# TC364_MainBoard_Singal_V2_0.net
KiCad netlist of a schematic drawn in Altium Designer
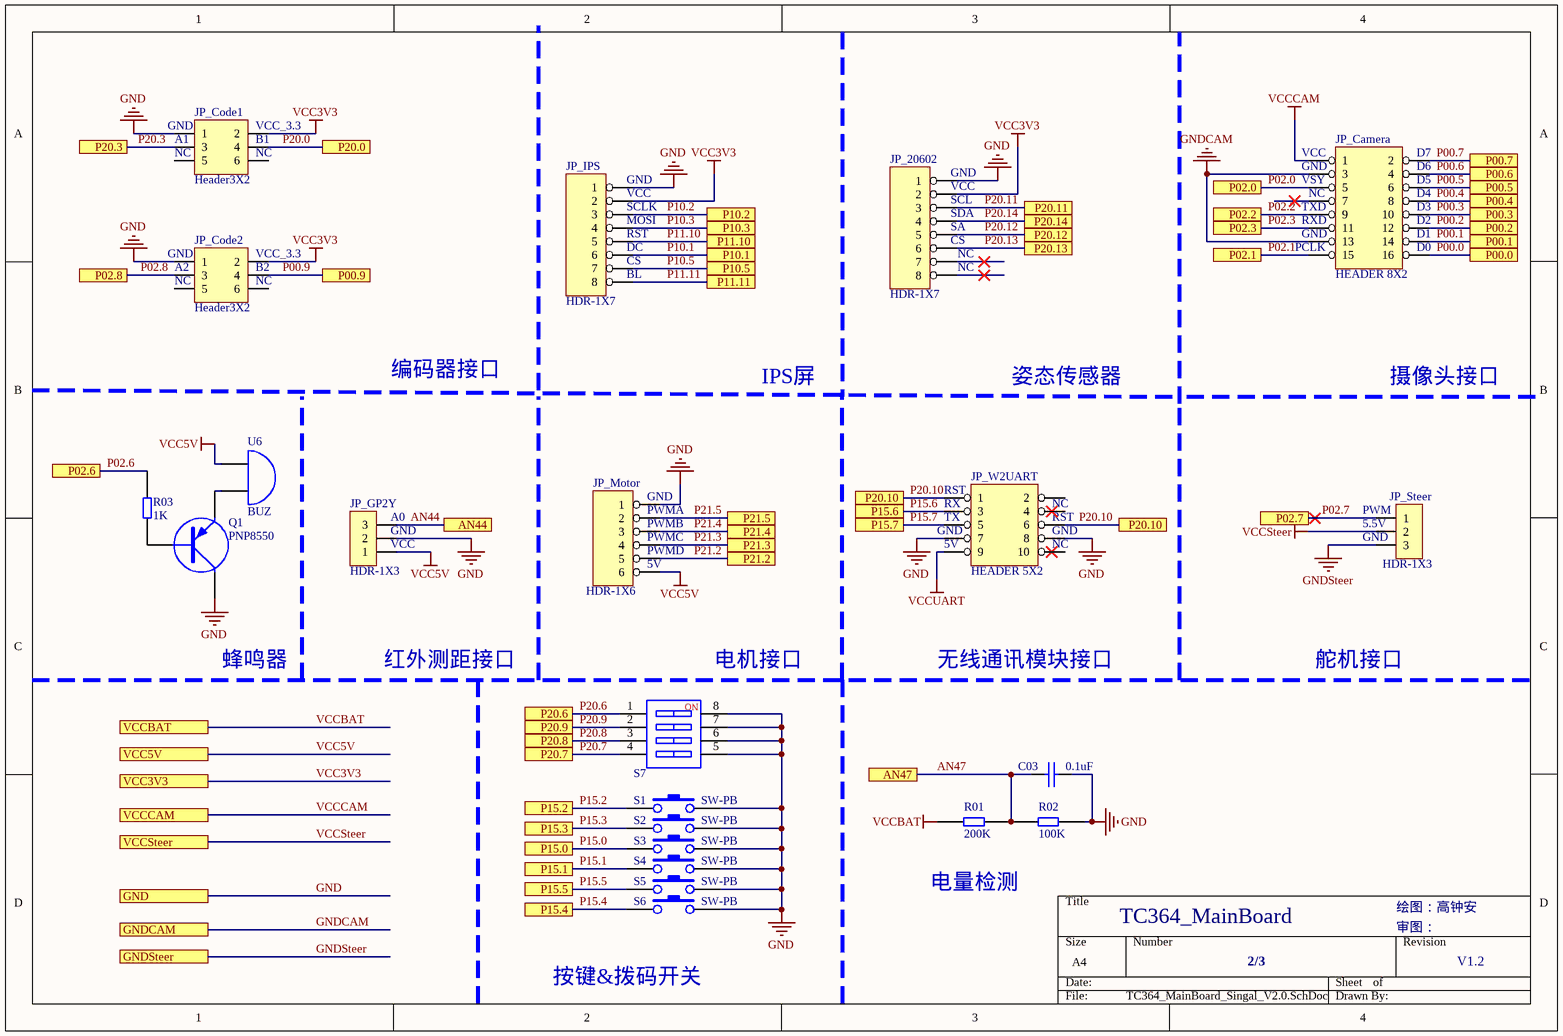
[diagram p0: TC364_MainBoard_Singal_V2.0.SchDoc]

(export (version "E")
  (design (tool "Eeschema 10.0.6"))
  (components
    (comp (ref "C03")
      (value "0.1uF")
      (footprint "0805C")
      (description "Capacitor")
      (libsource (lib "Protel99Lib_SCH") (part "CAP"))
    )
    (comp (ref "JP_20602")
      (value "HDR-1X7")
      (footprint "SIP8")
      (description "8 Pin Header")
      (libsource (lib "Protel99Lib_SCH") (part "8 HEADER"))
    )
    (comp (ref "JP_Camera")
      (value "HEADER 8X2")
      (footprint "IDC16-JLC - duplicate")
      (libsource (lib "Protel99Lib_SCH") (part "HEADER 8X2"))
    )
    (comp (ref "JP_Code1")
      (value "Header3X2")
      (footprint "HDR2.54-LI-2x3P")
      (description "3*2P接插件")
      (fields (field (name "版权归属") "封装库来自淘宝 ID：黄晶宝石"))
      (libsource (lib "5.3 - 接插件-脚距2.54 (100mil) ") (part "Header 3X2"))
    )
    (comp (ref "JP_Code2")
      (value "Header3X2")
      (footprint "HDR2.54-LI-2x3P")
      (description "3*2P接插件")
      (fields (field (name "版权归属") "封装库来自淘宝 ID：黄晶宝石"))
      (libsource (lib "5.3 - 接插件-脚距2.54 (100mil) ") (part "Header 3X2"))
    )
    (comp (ref "JP_GP2Y")
      (value "HDR-1X3")
      (footprint "SIP3N")
      (description "3P接插件")
      (fields (field (name "版权归属") "封装库来自淘宝 ID：黄晶宝石"))
      (libsource (lib "5.3 - 接插件-脚距2.54 (100mil) ") (part "Header 3"))
    )
    (comp (ref "JP_IPS")
      (value "HDR-1X7")
      (footprint "SIP8")
      (description "8 Pin Header")
      (libsource (lib "Protel99Lib_SCH") (part "8 HEADER"))
    )
    (comp (ref "JP_Motor")
      (value "HDR-1X6")
      (footprint "SIP6N")
      (libsource (lib "Protel99Lib_SCH") (part "HEADER 6"))
    )
    (comp (ref "JP_Steer")
      (value "HDR-1X3")
      (footprint "HDR2.54-LI-3P")
      (description "3P接插件")
      (fields (field (name "版权归属") "封装库来自淘宝 ID：黄晶宝石"))
      (libsource (lib "") (part "Header 3_1"))
    )
    (comp (ref "JP_W2UART")
      (value "HEADER 5X2")
      (footprint "IDC10-JLC")
      (libsource (lib "Protel99Lib_SCH") (part "HEADER 5X2"))
    )
    (comp (ref "Q1")
      (value "PNP8550")
      (footprint "PNP8550-SO")
      (description "PNP Transistor")
      (libsource (lib "Protel99Lib_SCH") (part "PNP"))
    )
    (comp (ref "R01") (value "200K") (footprint "0805R") (libsource (lib "BaseLib_SCH") (part "RES")))
    (comp (ref "R02") (value "100K") (footprint "0805R") (libsource (lib "BaseLib_SCH") (part "RES")))
    (comp (ref "R03") (value "1K") (footprint "0805R") (libsource (lib "BaseLib_SCH") (part "RES")))
    (comp (ref "S1")
      (value "SW-PB")
      (footprint "KEY2-6X3")
      (description "按键")
      (libsource (lib "jianing") (part "SW-PB"))
    )
    (comp (ref "S2")
      (value "SW-PB")
      (footprint "KEY2-6X3")
      (description "按键")
      (libsource (lib "jianing") (part "SW-PB"))
    )
    (comp (ref "S3")
      (value "SW-PB")
      (footprint "KEY2-6X3")
      (description "按键")
      (libsource (lib "jianing") (part "SW-PB"))
    )
    (comp (ref "S4")
      (value "SW-PB")
      (footprint "KEY2-6X3")
      (description "按键")
      (libsource (lib "jianing") (part "SW-PB"))
    )
    (comp (ref "S5")
      (value "SW-PB")
      (footprint "KEY2-6X3")
      (description "按键")
      (libsource (lib "jianing") (part "SW-PB"))
    )
    (comp (ref "S6")
      (value "SW-PB")
      (footprint "KEY2-6X3")
      (description "按键")
      (libsource (lib "jianing") (part "SW-PB"))
    )
    (comp (ref "S7")
      (value "SW-4P")
      (footprint "CSW DIP-4P")
      (description "4路编码开关")
      (libsource (lib "0.7 - 常用按键-开关") (part "SW-4P"))
    )
    (comp (ref "U6")
      (value "BUZ")
      (footprint "BUZ")
      (description "Bell")
      (libsource (lib "Protel99Lib_SCH") (part "BELL"))
    )
  )
  (nets
    (net (code "2") (name "/AN44") (class "Default")
      (node (ref "JP_GP2Y") (pin "3") (pinfunction "3_3") (pintype "passive"))
    )
    (net (code "3") (name "/AN47") (class "Default")
      (node (ref "C03") (pin "1") (pinfunction "1_1") (pintype "passive"))
      (node (ref "R01") (pin "1") (pinfunction "1_1") (pintype "passive"))
      (node (ref "R02") (pin "2") (pinfunction "2_2") (pintype "passive"))
    )
    (net (code "4") (name "/P00.0") (class "Default")
      (node (ref "JP_Camera") (pin "16") (pinfunction "16_16") (pintype "passive"))
    )
    (net (code "5") (name "/P00.1") (class "Default")
      (node (ref "JP_Camera") (pin "14") (pinfunction "14_14") (pintype "passive"))
    )
    (net (code "6") (name "/P00.2") (class "Default")
      (node (ref "JP_Camera") (pin "12") (pinfunction "12_12") (pintype "passive"))
    )
    (net (code "7") (name "/P00.3") (class "Default")
      (node (ref "JP_Camera") (pin "10") (pinfunction "10_10") (pintype "passive"))
    )
    (net (code "8") (name "/P00.4") (class "Default")
      (node (ref "JP_Camera") (pin "8") (pinfunction "8_8") (pintype "passive"))
    )
    (net (code "9") (name "/P00.5") (class "Default")
      (node (ref "JP_Camera") (pin "6") (pinfunction "6_6") (pintype "passive"))
    )
    (net (code "10") (name "/P00.6") (class "Default")
      (node (ref "JP_Camera") (pin "4") (pinfunction "4_4") (pintype "passive"))
    )
    (net (code "11") (name "/P00.7") (class "Default")
      (node (ref "JP_Camera") (pin "2") (pinfunction "2_2") (pintype "passive"))
    )
    (net (code "12") (name "/P00.9") (class "Default")
      (node (ref "JP_Code2") (pin "4") (pinfunction "4_4") (pintype "passive"))
    )
    (net (code "13") (name "/P02.0") (class "Default")
      (node (ref "JP_Camera") (pin "5") (pinfunction "5_5") (pintype "passive"))
    )
    (net (code "14") (name "/P02.1") (class "Default")
      (node (ref "JP_Camera") (pin "15") (pinfunction "15_15") (pintype "passive"))
    )
    (net (code "15") (name "/P02.2") (class "Default")
      (node (ref "JP_Camera") (pin "9") (pinfunction "9_9") (pintype "passive"))
    )
    (net (code "16") (name "/P02.3") (class "Default")
      (node (ref "JP_Camera") (pin "11") (pinfunction "11_11") (pintype "passive"))
    )
    (net (code "17") (name "/P02.6") (class "Default")
      (node (ref "R03") (pin "1") (pinfunction "1_1") (pintype "passive"))
    )
    (net (code "18") (name "/P02.7") (class "Default")
      (node (ref "JP_Steer") (pin "1") (pinfunction "1_1") (pintype "passive"))
    )
    (net (code "19") (name "/P02.8") (class "Default")
      (node (ref "JP_Code2") (pin "3") (pinfunction "3_3") (pintype "passive"))
    )
    (net (code "20") (name "/P10.1") (class "Default")
      (node (ref "JP_IPS") (pin "6") (pinfunction "6_6") (pintype "passive"))
    )
    (net (code "21") (name "/P10.2") (class "Default")
      (node (ref "JP_IPS") (pin "3") (pinfunction "3_3") (pintype "passive"))
    )
    (net (code "22") (name "/P10.3") (class "Default")
      (node (ref "JP_IPS") (pin "4") (pinfunction "4_4") (pintype "passive"))
    )
    (net (code "23") (name "/P10.5") (class "Default")
      (node (ref "JP_IPS") (pin "7") (pinfunction "7_7") (pintype "passive"))
    )
    (net (code "24") (name "/P11.10") (class "Default")
      (node (ref "JP_IPS") (pin "5") (pinfunction "5_5") (pintype "passive"))
    )
    (net (code "25") (name "/P11.11") (class "Default")
      (node (ref "JP_IPS") (pin "8") (pinfunction "8_8") (pintype "passive"))
    )
    (net (code "26") (name "/P15.0") (class "Default")
      (node (ref "S3") (pin "1") (pinfunction "1_1") (pintype "passive"))
    )
    (net (code "27") (name "/P15.1") (class "Default")
      (node (ref "S4") (pin "1") (pinfunction "1_1") (pintype "passive"))
    )
    (net (code "28") (name "/P15.2") (class "Default")
      (node (ref "S1") (pin "1") (pinfunction "1_1") (pintype "passive"))
    )
    (net (code "29") (name "/P15.3") (class "Default")
      (node (ref "S2") (pin "1") (pinfunction "1_1") (pintype "passive"))
    )
    (net (code "30") (name "/P15.4") (class "Default")
      (node (ref "S6") (pin "1") (pinfunction "1_1") (pintype "passive"))
    )
    (net (code "31") (name "/P15.5") (class "Default")
      (node (ref "S5") (pin "1") (pinfunction "1_1") (pintype "passive"))
    )
    (net (code "32") (name "/P15.6") (class "Default")
      (node (ref "JP_W2UART") (pin "3") (pinfunction "3_3") (pintype "passive"))
    )
    (net (code "33") (name "/P15.7") (class "Default")
      (node (ref "JP_W2UART") (pin "5") (pinfunction "5_5") (pintype "passive"))
    )
    (net (code "34") (name "/P20.0") (class "Default")
      (node (ref "JP_Code1") (pin "4") (pinfunction "4_4") (pintype "passive"))
    )
    (net (code "35") (name "/P20.3") (class "Default")
      (node (ref "JP_Code1") (pin "3") (pinfunction "3_3") (pintype "passive"))
    )
    (net (code "36") (name "/P20.6") (class "Default")
      (node (ref "S7") (pin "1") (pinfunction "1_1") (pintype "passive"))
    )
    (net (code "37") (name "/P20.7") (class "Default")
      (node (ref "S7") (pin "4") (pinfunction "4_4") (pintype "passive"))
    )
    (net (code "38") (name "/P20.8") (class "Default")
      (node (ref "S7") (pin "3") (pinfunction "3_3") (pintype "passive"))
    )
    (net (code "39") (name "/P20.9") (class "Default")
      (node (ref "S7") (pin "2") (pinfunction "2_2") (pintype "passive"))
    )
    (net (code "40") (name "/P20.10") (class "Default")
      (node (ref "JP_W2UART") (pin "1") (pinfunction "1_1") (pintype "passive"))
      (node (ref "JP_W2UART") (pin "6") (pinfunction "6_6") (pintype "passive"))
    )
    (net (code "41") (name "/P20.11") (class "Default")
      (node (ref "JP_20602") (pin "3") (pinfunction "3_3") (pintype "passive"))
    )
    (net (code "42") (name "/P20.12") (class "Default")
      (node (ref "JP_20602") (pin "5") (pinfunction "5_5") (pintype "passive"))
    )
    (net (code "43") (name "/P20.13") (class "Default")
      (node (ref "JP_20602") (pin "6") (pinfunction "6_6") (pintype "passive"))
    )
    (net (code "44") (name "/P20.14") (class "Default")
      (node (ref "JP_20602") (pin "4") (pinfunction "4_4") (pintype "passive"))
    )
    (net (code "45") (name "/P21.2") (class "Default")
      (node (ref "JP_Motor") (pin "5") (pinfunction "5_5") (pintype "passive"))
    )
    (net (code "46") (name "/P21.3") (class "Default")
      (node (ref "JP_Motor") (pin "4") (pinfunction "4_4") (pintype "passive"))
    )
    (net (code "47") (name "/P21.4") (class "Default")
      (node (ref "JP_Motor") (pin "3") (pinfunction "3_3") (pintype "passive"))
    )
    (net (code "48") (name "/P21.5") (class "Default")
      (node (ref "JP_Motor") (pin "2") (pinfunction "2_2") (pintype "passive"))
    )
    (net (code "49") (name "GND") (class "Default")
      (node (ref "C03") (pin "2") (pinfunction "2_2") (pintype "passive"))
      (node (ref "JP_20602") (pin "1") (pinfunction "1_1") (pintype "passive"))
      (node (ref "JP_Code1") (pin "1") (pinfunction "1_1") (pintype "passive"))
      (node (ref "JP_Code2") (pin "1") (pinfunction "1_1") (pintype "passive"))
      (node (ref "JP_GP2Y") (pin "2") (pinfunction "2_2") (pintype "passive"))
      (node (ref "JP_IPS") (pin "1") (pinfunction "1_1") (pintype "passive"))
      (node (ref "JP_Motor") (pin "1") (pinfunction "1_1") (pintype "passive"))
      (node (ref "JP_W2UART") (pin "7") (pinfunction "7_7") (pintype "passive"))
      (node (ref "JP_W2UART") (pin "8") (pinfunction "8_8") (pintype "passive"))
      (node (ref "Q1") (pin "3") (pinfunction "C_3") (pintype "passive"))
      (node (ref "R02") (pin "1") (pinfunction "1_1") (pintype "passive"))
      (node (ref "S1") (pin "2") (pinfunction "2_2") (pintype "passive"))
      (node (ref "S2") (pin "2") (pinfunction "2_2") (pintype "passive"))
      (node (ref "S3") (pin "2") (pinfunction "2_2") (pintype "passive"))
      (node (ref "S4") (pin "2") (pinfunction "2_2") (pintype "passive"))
      (node (ref "S5") (pin "2") (pinfunction "2_2") (pintype "passive"))
      (node (ref "S6") (pin "2") (pinfunction "2_2") (pintype "passive"))
      (node (ref "S7") (pin "5") (pinfunction "5_5") (pintype "passive"))
      (node (ref "S7") (pin "6") (pinfunction "6_6") (pintype "passive"))
      (node (ref "S7") (pin "7") (pinfunction "7_7") (pintype "passive"))
      (node (ref "S7") (pin "8") (pinfunction "8_8") (pintype "passive"))
    )
    (net (code "50") (name "GNDCAM") (class "Default")
      (node (ref "JP_Camera") (pin "13") (pinfunction "13_13") (pintype "passive"))
      (node (ref "JP_Camera") (pin "3") (pinfunction "3_3") (pintype "passive"))
    )
    (net (code "51") (name "GNDSteer") (class "Default")
      (node (ref "JP_Steer") (pin "3") (pinfunction "3_3") (pintype "passive"))
    )
    (net (code "52") (name "Net-(Q1-B)") (class "Default")
      (node (ref "Q1") (pin "1") (pinfunction "B_1") (pintype "passive"))
      (node (ref "R03") (pin "2") (pinfunction "2_2") (pintype "passive"))
    )
    (net (code "53") (name "Net-(Q1-E)") (class "Default")
      (node (ref "Q1") (pin "2") (pinfunction "E_2") (pintype "passive"))
      (node (ref "U6") (pin "2") (pinfunction "B_2") (pintype "passive"))
    )
    (net (code "54") (name "VCC3V3") (class "Default")
      (node (ref "JP_20602") (pin "2") (pinfunction "2_2") (pintype "passive"))
      (node (ref "JP_Code1") (pin "2") (pinfunction "2_2") (pintype "passive"))
      (node (ref "JP_Code2") (pin "2") (pinfunction "2_2") (pintype "passive"))
      (node (ref "JP_IPS") (pin "2") (pinfunction "2_2") (pintype "passive"))
    )
    (net (code "55") (name "VCC5V") (class "Default")
      (node (ref "JP_GP2Y") (pin "1") (pinfunction "1_1") (pintype "passive"))
      (node (ref "JP_Motor") (pin "6") (pinfunction "6_6") (pintype "passive"))
      (node (ref "U6") (pin "1") (pinfunction "A_1") (pintype "passive"))
    )
    (net (code "56") (name "VCCBAT") (class "Default")
      (node (ref "R01") (pin "2") (pinfunction "2_2") (pintype "passive"))
    )
    (net (code "57") (name "VCCCAM") (class "Default")
      (node (ref "JP_Camera") (pin "1") (pinfunction "1_1") (pintype "passive"))
    )
    (net (code "58") (name "VCCSteer") (class "Default")
      (node (ref "JP_Steer") (pin "2") (pinfunction "2_2") (pintype "passive"))
    )
    (net (code "59") (name "VCCUART") (class "Default")
      (node (ref "JP_W2UART") (pin "9") (pinfunction "9_9") (pintype "passive"))
    )
    (net (code "60") (name "unconnected-(JP_20602-Pad7)") (class "Default")
      (node (ref "JP_20602") (pin "7") (pinfunction "7_7") (pintype "passive"))
    )
    (net (code "61") (name "unconnected-(JP_20602-Pad8)") (class "Default")
      (node (ref "JP_20602") (pin "8") (pinfunction "8_8") (pintype "passive"))
    )
    (net (code "62") (name "unconnected-(JP_Camera-Pad7)") (class "Default")
      (node (ref "JP_Camera") (pin "7") (pinfunction "7_7") (pintype "passive"))
    )
    (net (code "63") (name "unconnected-(JP_Code1-Pad5)") (class "Default")
      (node (ref "JP_Code1") (pin "5") (pinfunction "5_5") (pintype "passive"))
    )
    (net (code "64") (name "unconnected-(JP_Code1-Pad6)") (class "Default")
      (node (ref "JP_Code1") (pin "6") (pinfunction "6_6") (pintype "passive"))
    )
    (net (code "65") (name "unconnected-(JP_Code2-Pad5)") (class "Default")
      (node (ref "JP_Code2") (pin "5") (pinfunction "5_5") (pintype "passive"))
    )
    (net (code "66") (name "unconnected-(JP_Code2-Pad6)") (class "Default")
      (node (ref "JP_Code2") (pin "6") (pinfunction "6_6") (pintype "passive"))
    )
    (net (code "67") (name "unconnected-(JP_W2UART-Pad2)") (class "Default")
      (node (ref "JP_W2UART") (pin "2") (pinfunction "2_2") (pintype "passive"))
    )
    (net (code "68") (name "unconnected-(JP_W2UART-Pad4)") (class "Default")
      (node (ref "JP_W2UART") (pin "4") (pinfunction "4_4") (pintype "passive"))
    )
    (net (code "69") (name "unconnected-(JP_W2UART-Pad10)") (class "Default")
      (node (ref "JP_W2UART") (pin "10") (pinfunction "10_10") (pintype "passive"))
    )
  )
)
